# mitutoyo_interface.net
KiCad netlist of a schematic drawn in EAGLE
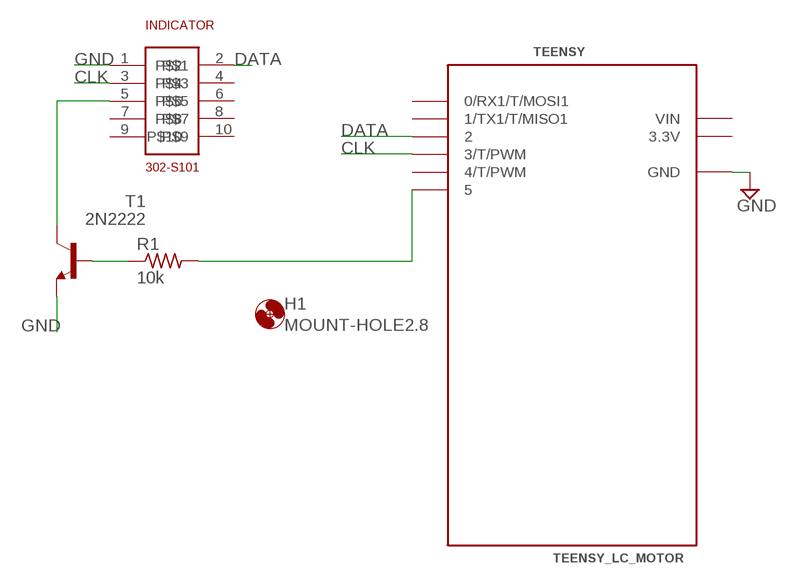
[diagram p0: schematic, sheet 1]

(export (version "E")
  (design (tool "Eeschema 10.0.6"))
  (components
    (comp (ref "H1")
      (value "MOUNT-HOLE2.8")
      (footprint "eagle-import:2,8")
      (libsource (lib "eagle-import") (part "MOUNT-HOLE2.8"))
    )
    (comp (ref "INDICATOR")
      (value "302-S101")
      (footprint "eagle-import:302-S101")
      (libsource (lib "eagle-import") (part "302-S101"))
    )
    (comp (ref "R1")
      (value "10k")
      (footprint "eagle-import:R0805")
      (libsource (lib "eagle-import") (part "R-US_R0805"))
    )
    (comp (ref "T1")
      (value "2N2222")
      (footprint "eagle-import:TO92-EBC-OVAL")
      (libsource (lib "eagle-import") (part "2N2222"))
    )
    (comp (ref "TEENSY")
      (value "TEENSY_LC_MOTOR")
      (footprint "eagle-import:TEENSYLC-MOTOR")
      (libsource (lib "eagle-import") (part "TEENSY_LC_MOTOR"))
    )
  )
  (nets
    (net (code "1") (name "/3.3V") (class "Default")
      (node (ref "TEENSY") (pin "3.3V") (pinfunction "3.3V_3.3V") (pintype "power_in"))
    )
    (net (code "2") (name "/CLK") (class "Default")
      (node (ref "INDICATOR") (pin "3") (pinfunction "P$3_3") (pintype "bidirectional"))
      (node (ref "TEENSY") (pin "3") (pinfunction "3/T/PWM_3") (pintype "bidirectional"))
    )
    (net (code "3") (name "/DATA") (class "Default")
      (node (ref "INDICATOR") (pin "2") (pinfunction "P$2_2") (pintype "bidirectional"))
      (node (ref "TEENSY") (pin "2") (pinfunction "2_2") (pintype "bidirectional"))
    )
    (net (code "4") (name "/VIN") (class "Default")
      (node (ref "TEENSY") (pin "VIN") (pinfunction "VIN_VIN") (pintype "power_in"))
    )
    (net (code "5") (name "GND") (class "Default")
      (node (ref "INDICATOR") (pin "1") (pinfunction "P$1_1") (pintype "bidirectional"))
      (node (ref "T1") (pin "E") (pinfunction "E_E") (pintype "passive"))
      (node (ref "TEENSY") (pin "GND") (pinfunction "GND_GND") (pintype "power_in"))
    )
    (net (code "6") (name "Net-(INDICATOR-P$5)") (class "Default")
      (node (ref "INDICATOR") (pin "5") (pinfunction "P$5_5") (pintype "bidirectional"))
      (node (ref "T1") (pin "C") (pinfunction "C_C") (pintype "passive"))
    )
    (net (code "7") (name "Net-(R1-Pad1)") (class "Default")
      (node (ref "R1") (pin "1") (pinfunction "1_1") (pintype "passive"))
      (node (ref "T1") (pin "B") (pinfunction "B_B") (pintype "passive"))
    )
    (net (code "8") (name "Net-(R1-Pad2)") (class "Default")
      (node (ref "R1") (pin "2") (pinfunction "2_2") (pintype "passive"))
      (node (ref "TEENSY") (pin "5") (pinfunction "5_5") (pintype "bidirectional"))
    )
    (net (code "9") (name "unconnected-(INDICATOR-P$4-Pad4)") (class "Default")
      (node (ref "INDICATOR") (pin "4") (pinfunction "P$4_4") (pintype "bidirectional"))
    )
    (net (code "10") (name "unconnected-(INDICATOR-P$6-Pad6)") (class "Default")
      (node (ref "INDICATOR") (pin "6") (pinfunction "P$6_6") (pintype "bidirectional"))
    )
    (net (code "11") (name "unconnected-(INDICATOR-P$7-Pad7)") (class "Default")
      (node (ref "INDICATOR") (pin "7") (pinfunction "P$7_7") (pintype "bidirectional"))
    )
    (net (code "12") (name "unconnected-(INDICATOR-P$8-Pad8)") (class "Default")
      (node (ref "INDICATOR") (pin "8") (pinfunction "P$8_8") (pintype "bidirectional"))
    )
    (net (code "13") (name "unconnected-(INDICATOR-P$9-Pad9)") (class "Default")
      (node (ref "INDICATOR") (pin "9") (pinfunction "P$9_9") (pintype "bidirectional"))
    )
    (net (code "14") (name "unconnected-(INDICATOR-P$10-Pad10)") (class "Default")
      (node (ref "INDICATOR") (pin "10") (pinfunction "P$10_10") (pintype "bidirectional"))
    )
    (net (code "15") (name "unconnected-(TEENSY-0{slash}RX1{slash}T{slash}MOSI1-Pad0)") (class "Default")
      (node (ref "TEENSY") (pin "0") (pinfunction "0/RX1/T/MOSI1_0") (pintype "bidirectional"))
    )
    (net (code "16") (name "unconnected-(TEENSY-1{slash}TX1{slash}T{slash}MISO1-Pad1)") (class "Default")
      (node (ref "TEENSY") (pin "1") (pinfunction "1/TX1/T/MISO1_1") (pintype "bidirectional"))
    )
    (net (code "17") (name "unconnected-(TEENSY-4{slash}T{slash}PWM-Pad4)") (class "Default")
      (node (ref "TEENSY") (pin "4") (pinfunction "4/T/PWM_4") (pintype "bidirectional"))
    )
  )
)
